# board1.net
KiCad netlist of a schematic drawn in EAGLE
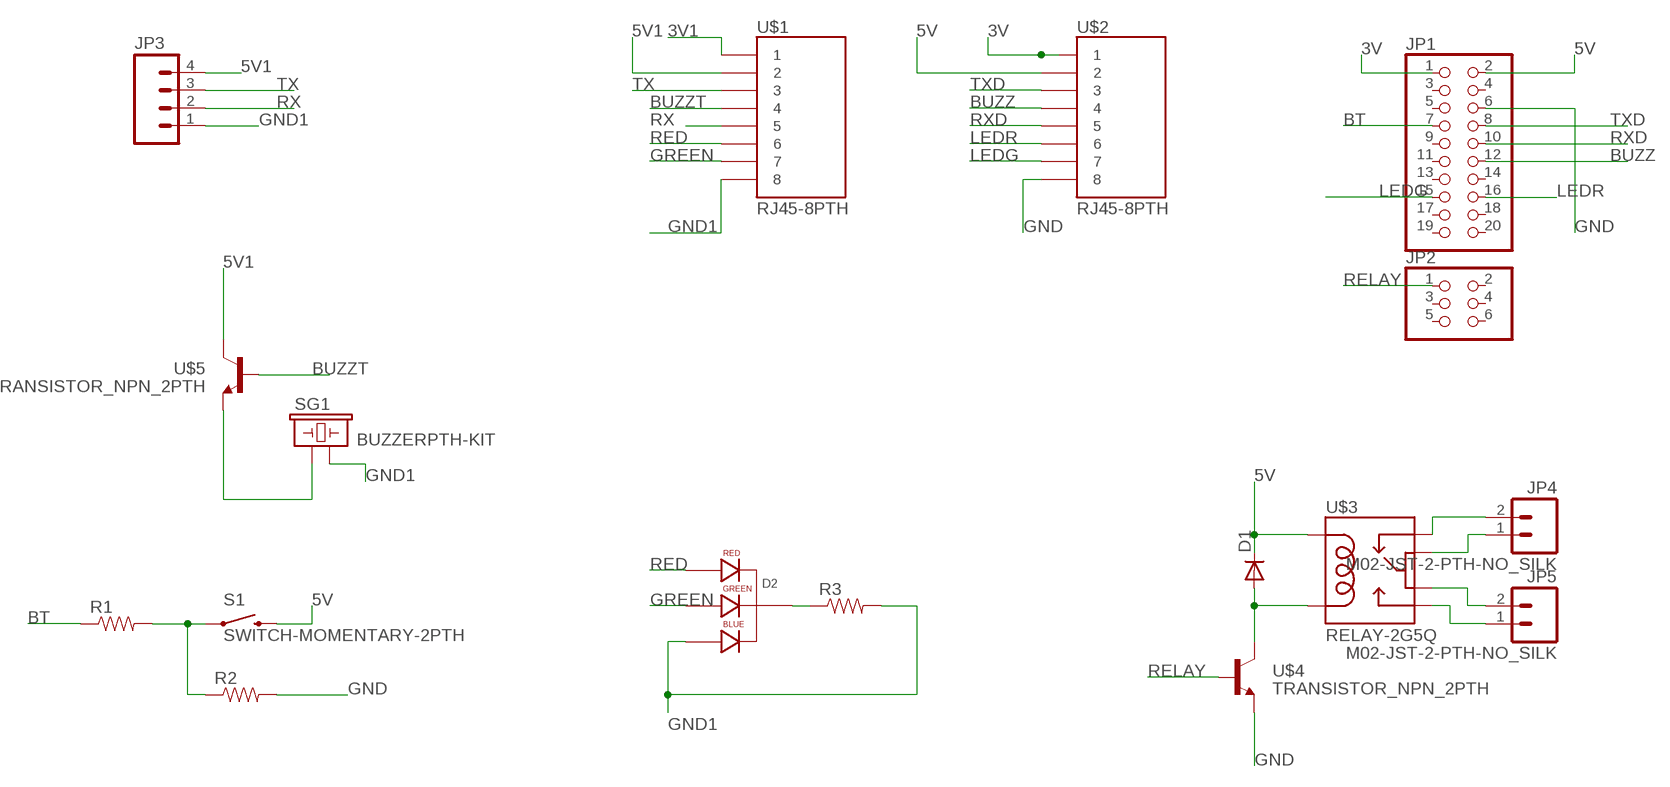
[diagram p0: schematic, sheet 1]

(export (version "E")
  (design (tool "Eeschema 10.0.6"))
  (components
    (comp (ref "D1")
      (value "DIODEPTH")
      (footprint "eagle-import:DIODE-1N4001")
      (libsource (lib "eagle-import") (part "DIODEPTH"))
    )
    (comp (ref "D2")
      (value "LED-RGB-CC-THRUCLEAR")
      (footprint "eagle-import:LED-RGB-THRU")
      (libsource (lib "eagle-import") (part "LED-RGB-CC-THRUCLEAR"))
    )
    (comp (ref "JP1")
      (value "PINHD-2X10")
      (footprint "eagle-import:2X10")
      (libsource (lib "eagle-import") (part "PINHD-2X10"))
    )
    (comp (ref "JP2")
      (value "PINHD-2X3")
      (footprint "eagle-import:2X03")
      (libsource (lib "eagle-import") (part "PINHD-2X3"))
    )
    (comp (ref "JP3")
      (value "M04PTH")
      (footprint "eagle-import:1X04")
      (libsource (lib "eagle-import") (part "M04PTH"))
    )
    (comp (ref "JP4")
      (value "M02-JST-2-PTH-NO_SILK")
      (footprint "eagle-import:JST-2-PTH-NS")
      (libsource (lib "eagle-import") (part "M02-JST-2-PTH-NO_SILK"))
    )
    (comp (ref "JP5")
      (value "M02-JST-2-PTH-NO_SILK")
      (footprint "eagle-import:JST-2-PTH-NS")
      (libsource (lib "eagle-import") (part "M02-JST-2-PTH-NO_SILK"))
    )
    (comp (ref "R1")
      (value "RESISTORPTH-1/4W")
      (footprint "eagle-import:AXIAL-0.4")
      (libsource (lib "eagle-import") (part "SparkFun-Resistors_RESISTORPTH-1/4W"))
    )
    (comp (ref "R2")
      (value "RESISTORPTH-1/4W")
      (footprint "eagle-import:AXIAL-0.4")
      (libsource (lib "eagle-import") (part "SparkFun-Resistors_RESISTORPTH-1/4W"))
    )
    (comp (ref "R3")
      (value "RESISTORPTH-1/4W")
      (footprint "eagle-import:AXIAL-0.4")
      (libsource (lib "eagle-import") (part "RESISTORPTH-1/4W"))
    )
    (comp (ref "S1")
      (value "SWITCH-MOMENTARY-2PTH")
      (footprint "eagle-import:TACTILE-PTH")
      (libsource (lib "eagle-import") (part "SWITCH-MOMENTARY-2PTH"))
    )
    (comp (ref "SG1")
      (value "BUZZERPTH-KIT")
      (footprint "eagle-import:BUZZER-12MM-KIT")
      (libsource (lib "eagle-import") (part "BUZZERPTH-KIT"))
    )
    (comp (ref "U$1")
      (value "RJ45-8PTH")
      (footprint "eagle-import:RJ45-8")
      (libsource (lib "eagle-import") (part "RJ45-8PTH"))
    )
    (comp (ref "U$2")
      (value "RJ45-8PTH")
      (footprint "eagle-import:RJ45-8")
      (libsource (lib "eagle-import") (part "RJ45-8PTH"))
    )
    (comp (ref "U$3")
      (value "RELAY-2G5Q")
      (footprint "eagle-import:RELAY-G5V")
      (libsource (lib "eagle-import") (part "RELAY-2G5Q"))
    )
    (comp (ref "U$4")
      (value "TRANSISTOR_NPN_2PTH")
      (footprint "eagle-import:TO-92")
      (libsource (lib "eagle-import") (part "TRANSISTOR_NPN_2PTH"))
    )
    (comp (ref "U$5")
      (value "TRANSISTOR_NPN_2PTH")
      (footprint "eagle-import:TO-92")
      (libsource (lib "eagle-import") (part "TRANSISTOR_NPN_2PTH"))
    )
  )
  (nets
    (net (code "1") (name "/3V") (class "Default")
      (node (ref "JP1") (pin "1") (pinfunction "1_1") (pintype "passive"))
      (node (ref "U$2") (pin "1") (pinfunction "1_1") (pintype "bidirectional"))
    )
    (net (code "2") (name "/3V1") (class "Default")
      (node (ref "U$1") (pin "1") (pinfunction "1_1") (pintype "bidirectional"))
    )
    (net (code "3") (name "/5V") (class "Default")
      (node (ref "D1") (pin "C") (pinfunction "C_C") (pintype "passive"))
      (node (ref "JP1") (pin "2") (pinfunction "2_2") (pintype "passive"))
      (node (ref "S1") (pin "3") (pinfunction "2_3") (pintype "passive"))
      (node (ref "U$2") (pin "2") (pinfunction "2_2") (pintype "bidirectional"))
      (node (ref "U$3") (pin "2") (pinfunction "2_2") (pintype "bidirectional"))
    )
    (net (code "4") (name "/5V1") (class "Default")
      (node (ref "JP3") (pin "4") (pinfunction "4_4") (pintype "passive"))
      (node (ref "U$1") (pin "2") (pinfunction "2_2") (pintype "bidirectional"))
      (node (ref "U$5") (pin "1") (pinfunction "C_1") (pintype "passive"))
    )
    (net (code "5") (name "/BT") (class "Default")
      (node (ref "JP1") (pin "7") (pinfunction "7_7") (pintype "passive"))
      (node (ref "R1") (pin "P$1") (pinfunction "1_P$1") (pintype "passive"))
    )
    (net (code "6") (name "/BUZZ") (class "Default")
      (node (ref "JP1") (pin "12") (pinfunction "12_12") (pintype "passive"))
      (node (ref "U$2") (pin "4") (pinfunction "4_4") (pintype "bidirectional"))
    )
    (net (code "7") (name "/BUZZT") (class "Default")
      (node (ref "U$1") (pin "4") (pinfunction "4_4") (pintype "bidirectional"))
      (node (ref "U$5") (pin "2") (pinfunction "B_2") (pintype "passive"))
    )
    (net (code "8") (name "/GND") (class "Default")
      (node (ref "JP1") (pin "6") (pinfunction "6_6") (pintype "passive"))
      (node (ref "R2") (pin "P$2") (pinfunction "2_P$2") (pintype "passive"))
      (node (ref "U$2") (pin "8") (pinfunction "8_8") (pintype "bidirectional"))
      (node (ref "U$4") (pin "3") (pinfunction "E_3") (pintype "passive"))
    )
    (net (code "9") (name "/GND1") (class "Default")
      (node (ref "D2") (pin "4") (pinfunction "BLUE_CATHODE_4") (pintype "bidirectional"))
      (node (ref "JP3") (pin "1") (pinfunction "1_1") (pintype "passive"))
      (node (ref "R3") (pin "P$2") (pinfunction "2_P$2") (pintype "passive"))
      (node (ref "SG1") (pin "-") (pinfunction "2_-") (pintype "passive"))
      (node (ref "U$1") (pin "8") (pinfunction "8_8") (pintype "bidirectional"))
    )
    (net (code "10") (name "/GREEN") (class "Default")
      (node (ref "D2") (pin "3") (pinfunction "GREEN_CATHODE_3") (pintype "bidirectional"))
      (node (ref "U$1") (pin "7") (pinfunction "7_7") (pintype "bidirectional"))
    )
    (net (code "11") (name "/LEDG") (class "Default")
      (node (ref "JP1") (pin "15") (pinfunction "15_15") (pintype "passive"))
      (node (ref "U$2") (pin "7") (pinfunction "7_7") (pintype "bidirectional"))
    )
    (net (code "12") (name "/LEDR") (class "Default")
      (node (ref "JP1") (pin "16") (pinfunction "16_16") (pintype "passive"))
      (node (ref "U$2") (pin "6") (pinfunction "6_6") (pintype "bidirectional"))
    )
    (net (code "13") (name "/RED") (class "Default")
      (node (ref "D2") (pin "1") (pinfunction "RED_CATHODE_1") (pintype "bidirectional"))
      (node (ref "U$1") (pin "6") (pinfunction "6_6") (pintype "bidirectional"))
    )
    (net (code "14") (name "/RELAY") (class "Default")
      (node (ref "JP2") (pin "1") (pinfunction "1_1") (pintype "passive"))
      (node (ref "U$4") (pin "2") (pinfunction "B_2") (pintype "passive"))
    )
    (net (code "15") (name "/RX") (class "Default")
      (node (ref "JP3") (pin "2") (pinfunction "2_2") (pintype "passive"))
      (node (ref "U$1") (pin "5") (pinfunction "5_5") (pintype "bidirectional"))
    )
    (net (code "16") (name "/RXD") (class "Default")
      (node (ref "JP1") (pin "10") (pinfunction "10_10") (pintype "passive"))
      (node (ref "U$2") (pin "5") (pinfunction "5_5") (pintype "bidirectional"))
    )
    (net (code "17") (name "/TX") (class "Default")
      (node (ref "JP3") (pin "3") (pinfunction "3_3") (pintype "passive"))
      (node (ref "U$1") (pin "3") (pinfunction "3_3") (pintype "bidirectional"))
    )
    (net (code "18") (name "/TXD") (class "Default")
      (node (ref "JP1") (pin "8") (pinfunction "8_8") (pintype "passive"))
      (node (ref "U$2") (pin "3") (pinfunction "3_3") (pintype "bidirectional"))
    )
    (net (code "19") (name "Net-(D2-CATHODE)") (class "Default")
      (node (ref "D2") (pin "2") (pinfunction "CATHODE_2") (pintype "bidirectional"))
      (node (ref "R3") (pin "P$1") (pinfunction "1_P$1") (pintype "passive"))
    )
    (net (code "20") (name "Net-(JP4-Pad1)") (class "Default")
      (node (ref "JP4") (pin "1") (pinfunction "1_1") (pintype "passive"))
      (node (ref "U$3") (pin "5") (pinfunction "5_5") (pintype "bidirectional"))
    )
    (net (code "21") (name "Net-(JP4-Pad2)") (class "Default")
      (node (ref "JP4") (pin "2") (pinfunction "2_2") (pintype "passive"))
      (node (ref "U$3") (pin "1") (pinfunction "1_1") (pintype "bidirectional"))
    )
    (net (code "22") (name "Net-(JP5-Pad1)") (class "Default")
      (node (ref "JP5") (pin "1") (pinfunction "1_1") (pintype "passive"))
      (node (ref "U$3") (pin "10") (pinfunction "10_10") (pintype "bidirectional"))
    )
    (net (code "23") (name "Net-(JP5-Pad2)") (class "Default")
      (node (ref "JP5") (pin "2") (pinfunction "2_2") (pintype "passive"))
      (node (ref "U$3") (pin "6") (pinfunction "6_6") (pintype "bidirectional"))
    )
    (net (code "24") (name "Net-(R1-2)") (class "Default")
      (node (ref "R1") (pin "P$2") (pinfunction "2_P$2") (pintype "passive"))
      (node (ref "R2") (pin "P$1") (pinfunction "1_P$1") (pintype "passive"))
      (node (ref "S1") (pin "1") (pinfunction "1_1") (pintype "passive"))
    )
    (net (code "25") (name "Net-(SG1-1)") (class "Default")
      (node (ref "SG1") (pin "+") (pinfunction "1_+") (pintype "passive"))
      (node (ref "U$5") (pin "3") (pinfunction "E_3") (pintype "passive"))
    )
    (net (code "26") (name "Net-(U$4-C)") (class "Default")
      (node (ref "D1") (pin "A") (pinfunction "A_A") (pintype "passive"))
      (node (ref "U$3") (pin "9") (pinfunction "9_9") (pintype "bidirectional"))
      (node (ref "U$4") (pin "1") (pinfunction "C_1") (pintype "passive"))
    )
    (net (code "27") (name "unconnected-(JP1-Pad3)") (class "Default")
      (node (ref "JP1") (pin "3") (pinfunction "3_3") (pintype "passive"))
    )
    (net (code "28") (name "unconnected-(JP1-Pad4)") (class "Default")
      (node (ref "JP1") (pin "4") (pinfunction "4_4") (pintype "passive"))
    )
    (net (code "29") (name "unconnected-(JP1-Pad5)") (class "Default")
      (node (ref "JP1") (pin "5") (pinfunction "5_5") (pintype "passive"))
    )
    (net (code "30") (name "unconnected-(JP1-Pad9)") (class "Default")
      (node (ref "JP1") (pin "9") (pinfunction "9_9") (pintype "passive"))
    )
    (net (code "31") (name "unconnected-(JP1-Pad11)") (class "Default")
      (node (ref "JP1") (pin "11") (pinfunction "11_11") (pintype "passive"))
    )
    (net (code "32") (name "unconnected-(JP1-Pad13)") (class "Default")
      (node (ref "JP1") (pin "13") (pinfunction "13_13") (pintype "passive"))
    )
    (net (code "33") (name "unconnected-(JP1-Pad14)") (class "Default")
      (node (ref "JP1") (pin "14") (pinfunction "14_14") (pintype "passive"))
    )
    (net (code "34") (name "unconnected-(JP1-Pad17)") (class "Default")
      (node (ref "JP1") (pin "17") (pinfunction "17_17") (pintype "passive"))
    )
    (net (code "35") (name "unconnected-(JP1-Pad18)") (class "Default")
      (node (ref "JP1") (pin "18") (pinfunction "18_18") (pintype "passive"))
    )
    (net (code "36") (name "unconnected-(JP1-Pad19)") (class "Default")
      (node (ref "JP1") (pin "19") (pinfunction "19_19") (pintype "passive"))
    )
    (net (code "37") (name "unconnected-(JP1-Pad20)") (class "Default")
      (node (ref "JP1") (pin "20") (pinfunction "20_20") (pintype "passive"))
    )
    (net (code "38") (name "unconnected-(JP2-Pad2)") (class "Default")
      (node (ref "JP2") (pin "2") (pinfunction "2_2") (pintype "passive"))
    )
    (net (code "39") (name "unconnected-(JP2-Pad3)") (class "Default")
      (node (ref "JP2") (pin "3") (pinfunction "3_3") (pintype "passive"))
    )
    (net (code "40") (name "unconnected-(JP2-Pad4)") (class "Default")
      (node (ref "JP2") (pin "4") (pinfunction "4_4") (pintype "passive"))
    )
    (net (code "41") (name "unconnected-(JP2-Pad5)") (class "Default")
      (node (ref "JP2") (pin "5") (pinfunction "5_5") (pintype "passive"))
    )
    (net (code "42") (name "unconnected-(JP2-Pad6)") (class "Default")
      (node (ref "JP2") (pin "6") (pinfunction "6_6") (pintype "passive"))
    )
  )
)
